# picaxe_funky.net
KiCad netlist of a schematic drawn in EAGLE
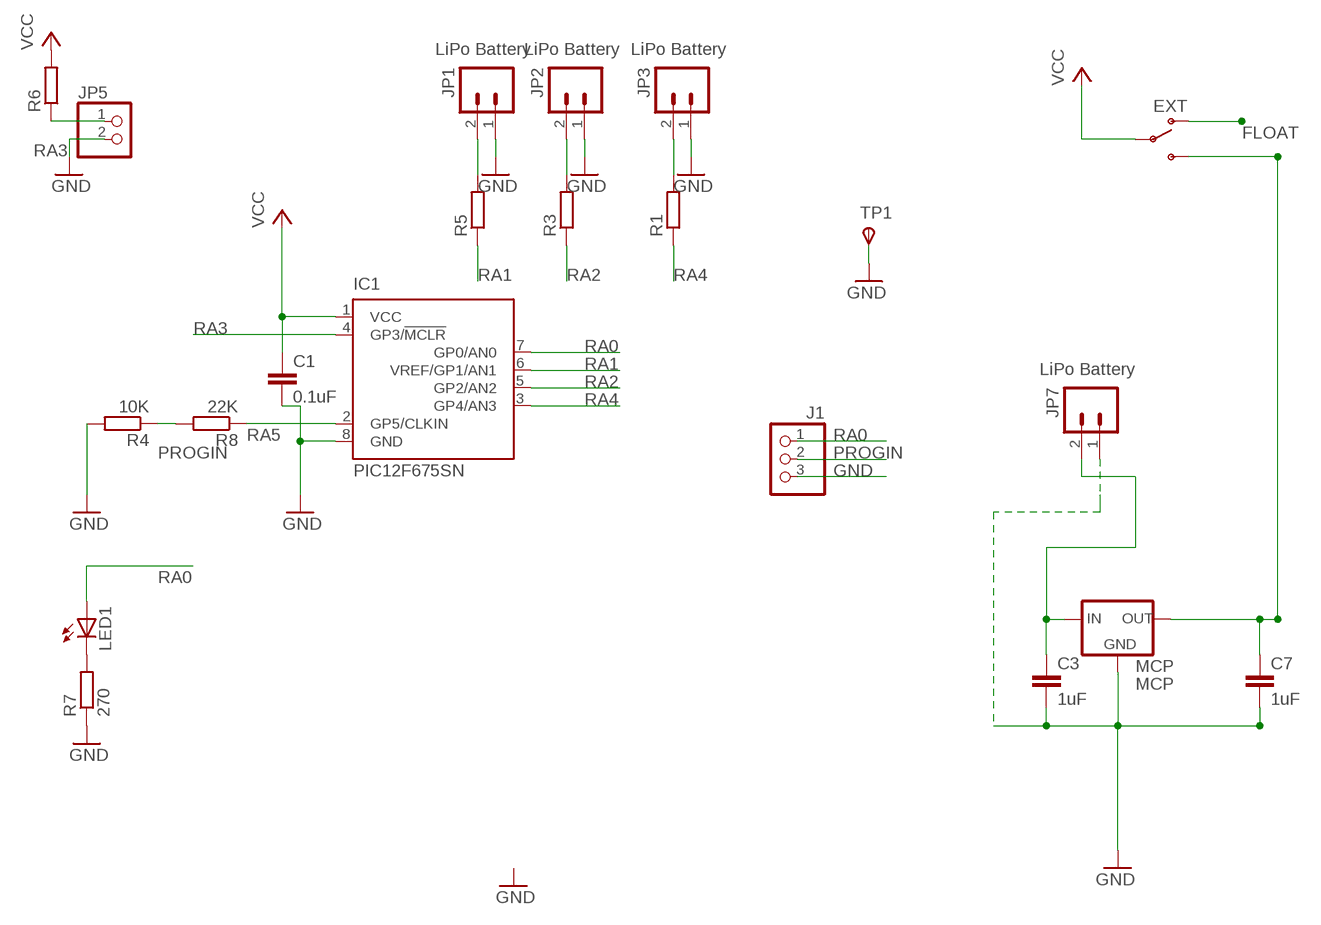
[diagram p0: schematic, sheet 1]

(export (version "E")
  (design (tool "Eeschema 10.0.6"))
  (components
    (comp (ref "C1")
      (value "0.1uF")
      (footprint "eagle-import:C0805")
      (libsource (lib "eagle-import") (part "C-EUC0805"))
    )
    (comp (ref "C3")
      (value "1uF")
      (footprint "eagle-import:C0805")
      (libsource (lib "eagle-import") (part "C-EUC0805"))
    )
    (comp (ref "C7")
      (value "1uF")
      (footprint "eagle-import:C0805")
      (libsource (lib "eagle-import") (part "C-EUC0805"))
    )
    (comp (ref "IC1")
      (value "PIC12F675SN")
      (footprint "eagle-import:SO-08")
      (fields (field (name "MF") "MICROCHIP") (field (name "MPN") "PIC12F675-E/SN"))
      (libsource (lib "eagle-import") (part "PIC12F675SN"))
    )
    (comp (ref "J1")
      (value "PINHD-1X3")
      (footprint "eagle-import:1X03")
      (libsource (lib "eagle-import") (part "PINHD-1X3"))
    )
    (comp (ref "JP1")
      (value "LiPo Battery")
      (footprint "eagle-import:JST-2-PTH")
      (libsource (lib "eagle-import") (part "M02JST-PTH-2"))
    )
    (comp (ref "JP2")
      (value "LiPo Battery")
      (footprint "eagle-import:JST-2-PTH")
      (libsource (lib "eagle-import") (part "M02JST-PTH-2"))
    )
    (comp (ref "JP3")
      (value "LiPo Battery")
      (footprint "eagle-import:JST-2-PTH")
      (libsource (lib "eagle-import") (part "M02JST-PTH-2"))
    )
    (comp (ref "JP5")
      (value "PINHD-1X2")
      (footprint "eagle-import:1X02")
      (libsource (lib "eagle-import") (part "PINHD-1X2"))
    )
    (comp (ref "JP7")
      (value "LiPo Battery")
      (footprint "eagle-import:JST-2-PTH")
      (libsource (lib "eagle-import") (part "M02JST-PTH-2"))
    )
    (comp (ref "LED1")
      (value "LEDCHIPLED_1206")
      (footprint "eagle-import:CHIPLED_1206")
      (libsource (lib "eagle-import") (part "LEDCHIPLED_1206"))
    )
    (comp (ref "MCP")
      (value "MCP")
      (footprint "eagle-import:SOT-23")
      (libsource (lib "eagle-import") (part "MCP1700SOT-23"))
    )
    (comp (ref "ON")
      (value "EXT")
      (footprint "eagle-import:SWITCH-SPDT")
      (libsource (lib "eagle-import") (part "SWITCH-SPSTPTH"))
    )
    (comp (ref "R1")
      (value "R-EU_R0805")
      (footprint "eagle-import:R0805")
      (libsource (lib "eagle-import") (part "R-EU_R0805"))
    )
    (comp (ref "R3")
      (value "R-EU_R0805")
      (footprint "eagle-import:R0805")
      (libsource (lib "eagle-import") (part "R-EU_R0805"))
    )
    (comp (ref "R4")
      (value "10K")
      (footprint "eagle-import:R0805")
      (libsource (lib "eagle-import") (part "R-EU_R0805"))
    )
    (comp (ref "R5")
      (value "R-EU_R0805")
      (footprint "eagle-import:R0805")
      (libsource (lib "eagle-import") (part "R-EU_R0805"))
    )
    (comp (ref "R6")
      (value "R-EU_R0805")
      (footprint "eagle-import:R0805")
      (libsource (lib "eagle-import") (part "R-EU_R0805"))
    )
    (comp (ref "R7")
      (value "270")
      (footprint "eagle-import:R0805")
      (libsource (lib "eagle-import") (part "R-EU_R0805"))
    )
    (comp (ref "R8")
      (value "22K")
      (footprint "eagle-import:R0805")
      (libsource (lib "eagle-import") (part "R-EU_R0805"))
    )
    (comp (ref "TP1")
      (value "TPSTP20R")
      (footprint "eagle-import:TP20R")
      (libsource (lib "eagle-import") (part "TPSTP20R"))
    )
  )
  (nets
    (net (code "1") (name "/FLOAT") (class "Default")
      (node (ref "ON") (pin "1") (pinfunction "O_1") (pintype "passive"))
    )
    (net (code "2") (name "/PROGIN") (class "Default")
      (node (ref "J1") (pin "2") (pinfunction "2_2") (pintype "passive"))
      (node (ref "R4") (pin "1") (pinfunction "1_1") (pintype "passive"))
      (node (ref "R8") (pin "2") (pinfunction "2_2") (pintype "passive"))
    )
    (net (code "3") (name "/RA0") (class "Default")
      (node (ref "IC1") (pin "7") (pinfunction "GP0/AN0_7") (pintype "bidirectional"))
      (node (ref "J1") (pin "1") (pinfunction "1_1") (pintype "passive"))
      (node (ref "LED1") (pin "A") (pinfunction "A_A") (pintype "passive"))
    )
    (net (code "4") (name "/RA1") (class "Default")
      (node (ref "IC1") (pin "6") (pinfunction "VREF/GP1/AN1_6") (pintype "bidirectional"))
      (node (ref "R5") (pin "1") (pinfunction "1_1") (pintype "passive"))
    )
    (net (code "5") (name "/RA2") (class "Default")
      (node (ref "IC1") (pin "5") (pinfunction "GP2/AN2_5") (pintype "bidirectional"))
      (node (ref "R3") (pin "1") (pinfunction "1_1") (pintype "passive"))
    )
    (net (code "6") (name "/RA3") (class "Default")
      (node (ref "IC1") (pin "4") (pinfunction "GP3/~{MCLR}_4") (pintype "input"))
      (node (ref "JP5") (pin "1") (pinfunction "1_1") (pintype "passive"))
      (node (ref "R6") (pin "1") (pinfunction "1_1") (pintype "passive"))
    )
    (net (code "7") (name "/RA4") (class "Default")
      (node (ref "IC1") (pin "3") (pinfunction "GP4/AN3_3") (pintype "bidirectional"))
      (node (ref "R1") (pin "1") (pinfunction "1_1") (pintype "passive"))
    )
    (net (code "8") (name "/RA5") (class "Default")
      (node (ref "IC1") (pin "2") (pinfunction "GP5/CLKIN_2") (pintype "bidirectional"))
      (node (ref "R8") (pin "1") (pinfunction "1_1") (pintype "passive"))
    )
    (net (code "9") (name "GND") (class "Default")
      (node (ref "C1") (pin "2") (pinfunction "2_2") (pintype "passive"))
      (node (ref "C3") (pin "2") (pinfunction "2_2") (pintype "passive"))
      (node (ref "C7") (pin "2") (pinfunction "2_2") (pintype "passive"))
      (node (ref "IC1") (pin "8") (pinfunction "GND_8") (pintype "power_in"))
      (node (ref "J1") (pin "3") (pinfunction "3_3") (pintype "passive"))
      (node (ref "JP1") (pin "1") (pinfunction "1_1") (pintype "passive"))
      (node (ref "JP2") (pin "1") (pinfunction "1_1") (pintype "passive"))
      (node (ref "JP3") (pin "1") (pinfunction "1_1") (pintype "passive"))
      (node (ref "JP5") (pin "2") (pinfunction "2_2") (pintype "passive"))
      (node (ref "JP7") (pin "1") (pinfunction "1_1") (pintype "passive"))
      (node (ref "MCP") (pin "1") (pinfunction "GND_1") (pintype "input"))
      (node (ref "R4") (pin "2") (pinfunction "2_2") (pintype "passive"))
      (node (ref "R7") (pin "1") (pinfunction "1_1") (pintype "passive"))
      (node (ref "TP1") (pin "TP") (pinfunction "PP_TP") (pintype "input"))
    )
    (net (code "10") (name "Net-(JP1-Pad2)") (class "Default")
      (node (ref "JP1") (pin "2") (pinfunction "2_2") (pintype "passive"))
      (node (ref "R5") (pin "2") (pinfunction "2_2") (pintype "passive"))
    )
    (net (code "11") (name "Net-(JP2-Pad2)") (class "Default")
      (node (ref "JP2") (pin "2") (pinfunction "2_2") (pintype "passive"))
      (node (ref "R3") (pin "2") (pinfunction "2_2") (pintype "passive"))
    )
    (net (code "12") (name "Net-(JP3-Pad2)") (class "Default")
      (node (ref "JP3") (pin "2") (pinfunction "2_2") (pintype "passive"))
      (node (ref "R1") (pin "2") (pinfunction "2_2") (pintype "passive"))
    )
    (net (code "13") (name "Net-(LED1-PadC)") (class "Default")
      (node (ref "LED1") (pin "C") (pinfunction "C_C") (pintype "passive"))
      (node (ref "R7") (pin "2") (pinfunction "2_2") (pintype "passive"))
    )
    (net (code "14") (name "Net-(MCP-IN)") (class "Default")
      (node (ref "C3") (pin "1") (pinfunction "1_1") (pintype "passive"))
      (node (ref "JP7") (pin "2") (pinfunction "2_2") (pintype "passive"))
      (node (ref "MCP") (pin "3") (pinfunction "IN_3") (pintype "input"))
    )
    (net (code "15") (name "Net-(MCP-OUT)") (class "Default")
      (node (ref "C7") (pin "1") (pinfunction "1_1") (pintype "passive"))
      (node (ref "MCP") (pin "2") (pinfunction "OUT_2") (pintype "passive"))
      (node (ref "ON") (pin "3") (pinfunction "S_3") (pintype "passive"))
    )
    (net (code "16") (name "VCC") (class "Default")
      (node (ref "C1") (pin "1") (pinfunction "1_1") (pintype "passive"))
      (node (ref "IC1") (pin "1") (pinfunction "VCC_1") (pintype "power_in"))
      (node (ref "ON") (pin "2") (pinfunction "P_2") (pintype "passive"))
      (node (ref "R6") (pin "2") (pinfunction "2_2") (pintype "passive"))
    )
  )
)
